# NumPad.net
KiCad netlist of a schematic drawn in EAGLE
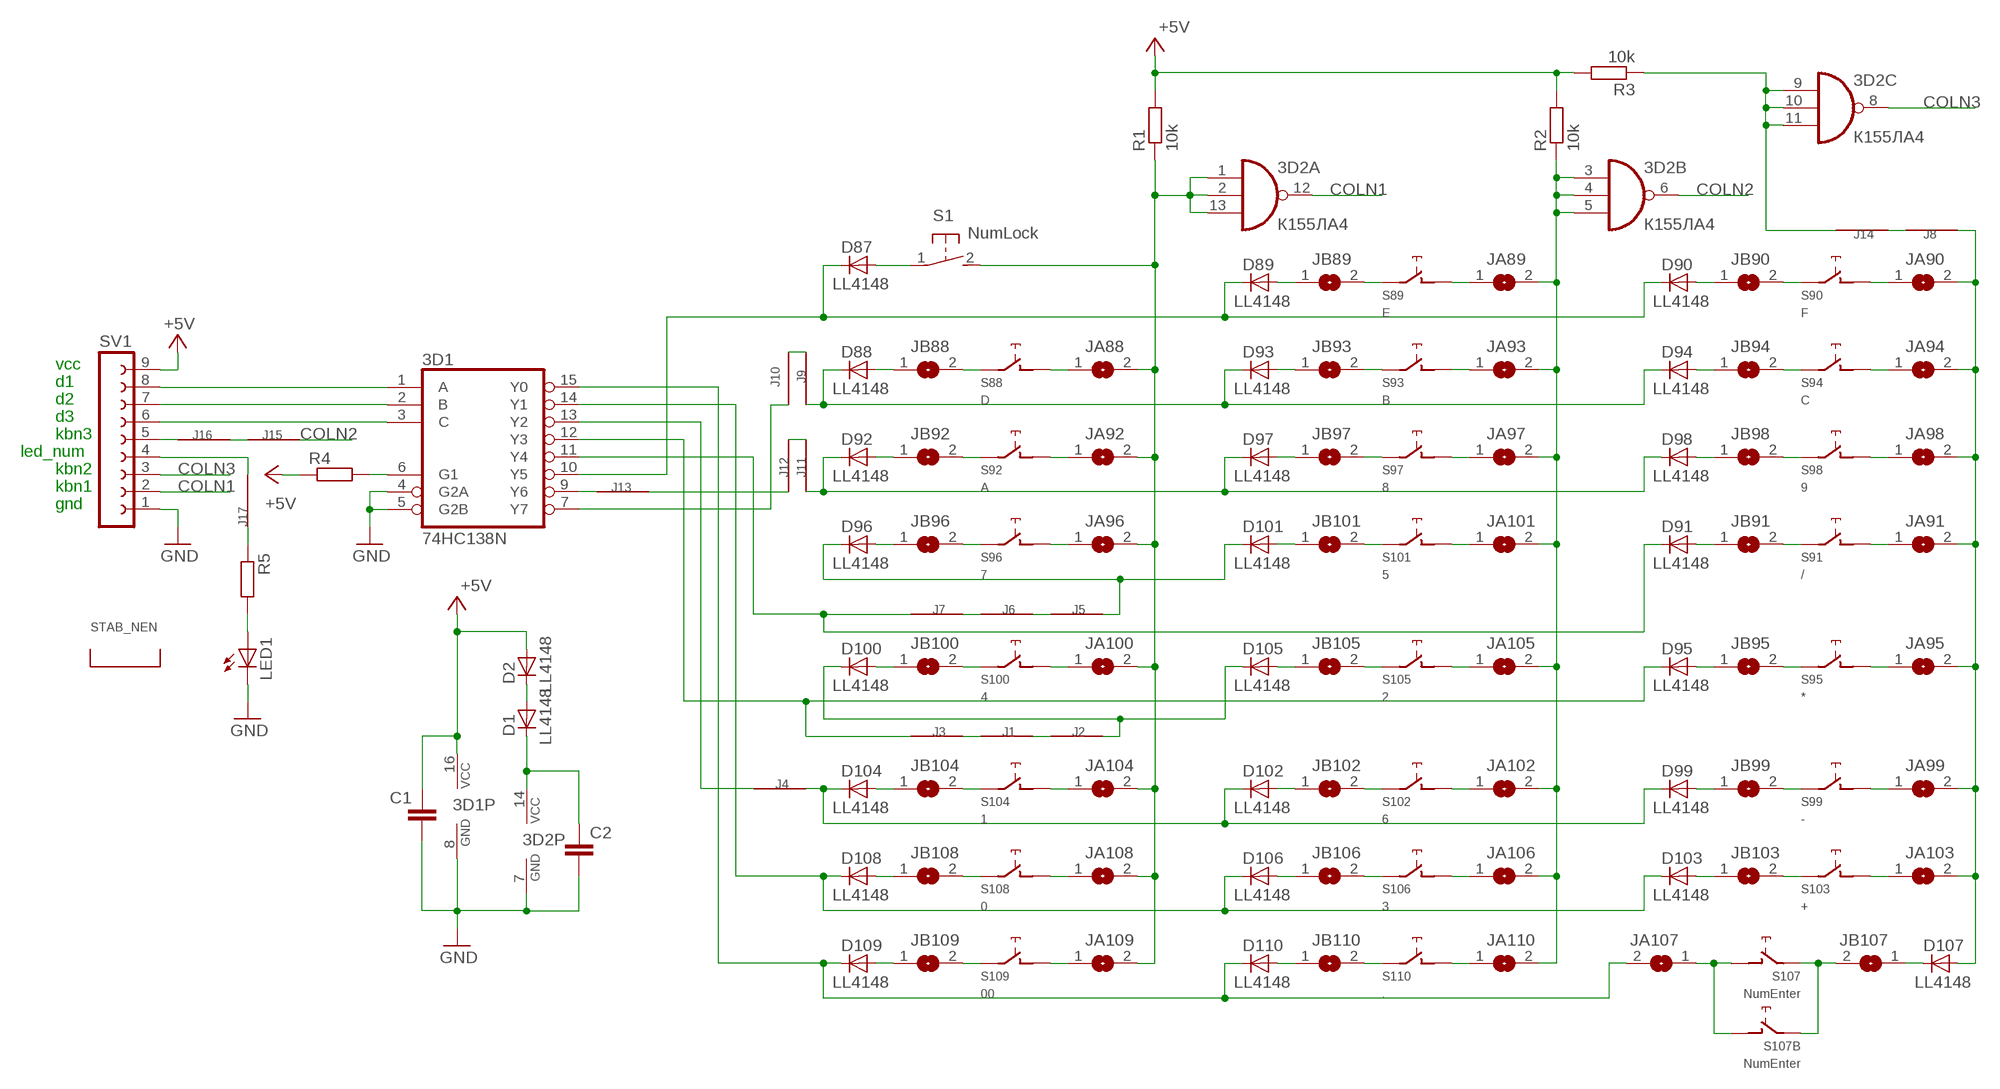
[diagram p0: schematic, sheet 1]

(export (version "E")
  (design (tool "Eeschema 10.0.6"))
  (components
    (comp (ref "3D1")
      (value "74HC138N")
      (footprint "eagle-import:DIL16")
      (libsource (lib "eagle-import") (part "74138NHC"))
    )
    (comp (ref "3D2")
      (value "К155ЛА4")
      (footprint "eagle-import:DIL14")
      (libsource (lib "eagle-import") (part "7410NHC"))
    )
    (comp (ref "C1")
      (value "C-EUC1206")
      (footprint "eagle-import:C1206")
      (libsource (lib "eagle-import") (part "C-EUC1206"))
    )
    (comp (ref "C2")
      (value "C-EUC1206")
      (footprint "eagle-import:C1206")
      (libsource (lib "eagle-import") (part "C-EUC1206"))
    )
    (comp (ref "D1")
      (value "LL4148")
      (footprint "eagle-import:SOD80C")
      (libsource (lib "eagle-import") (part "LL4148"))
    )
    (comp (ref "D2")
      (value "LL4148")
      (footprint "eagle-import:SOD80C")
      (libsource (lib "eagle-import") (part "LL4148"))
    )
    (comp (ref "D87")
      (value "LL4148")
      (footprint "eagle-import:SOD80C")
      (libsource (lib "eagle-import") (part "LL4148"))
    )
    (comp (ref "D88")
      (value "LL4148")
      (footprint "eagle-import:SOD80C")
      (libsource (lib "eagle-import") (part "LL4148"))
    )
    (comp (ref "D89")
      (value "LL4148")
      (footprint "eagle-import:SOD80C")
      (libsource (lib "eagle-import") (part "LL4148"))
    )
    (comp (ref "D90")
      (value "LL4148")
      (footprint "eagle-import:SOD80C")
      (libsource (lib "eagle-import") (part "LL4148"))
    )
    (comp (ref "D91")
      (value "LL4148")
      (footprint "eagle-import:SOD80C")
      (libsource (lib "eagle-import") (part "LL4148"))
    )
    (comp (ref "D92")
      (value "LL4148")
      (footprint "eagle-import:SOD80C")
      (libsource (lib "eagle-import") (part "LL4148"))
    )
    (comp (ref "D93")
      (value "LL4148")
      (footprint "eagle-import:SOD80C")
      (libsource (lib "eagle-import") (part "LL4148"))
    )
    (comp (ref "D94")
      (value "LL4148")
      (footprint "eagle-import:SOD80C")
      (libsource (lib "eagle-import") (part "LL4148"))
    )
    (comp (ref "D95")
      (value "LL4148")
      (footprint "eagle-import:SOD80C")
      (libsource (lib "eagle-import") (part "LL4148"))
    )
    (comp (ref "D96")
      (value "LL4148")
      (footprint "eagle-import:SOD80C")
      (libsource (lib "eagle-import") (part "LL4148"))
    )
    (comp (ref "D97")
      (value "LL4148")
      (footprint "eagle-import:SOD80C")
      (libsource (lib "eagle-import") (part "LL4148"))
    )
    (comp (ref "D98")
      (value "LL4148")
      (footprint "eagle-import:SOD80C")
      (libsource (lib "eagle-import") (part "LL4148"))
    )
    (comp (ref "D99")
      (value "LL4148")
      (footprint "eagle-import:SOD80C")
      (libsource (lib "eagle-import") (part "LL4148"))
    )
    (comp (ref "D100")
      (value "LL4148")
      (footprint "eagle-import:SOD80C")
      (libsource (lib "eagle-import") (part "LL4148"))
    )
    (comp (ref "D101")
      (value "LL4148")
      (footprint "eagle-import:SOD80C")
      (libsource (lib "eagle-import") (part "LL4148"))
    )
    (comp (ref "D102")
      (value "LL4148")
      (footprint "eagle-import:SOD80C")
      (libsource (lib "eagle-import") (part "LL4148"))
    )
    (comp (ref "D103")
      (value "LL4148")
      (footprint "eagle-import:SOD80C")
      (libsource (lib "eagle-import") (part "LL4148"))
    )
    (comp (ref "D104")
      (value "LL4148")
      (footprint "eagle-import:SOD80C")
      (libsource (lib "eagle-import") (part "LL4148"))
    )
    (comp (ref "D105")
      (value "LL4148")
      (footprint "eagle-import:SOD80C")
      (libsource (lib "eagle-import") (part "LL4148"))
    )
    (comp (ref "D106")
      (value "LL4148")
      (footprint "eagle-import:SOD80C")
      (libsource (lib "eagle-import") (part "LL4148"))
    )
    (comp (ref "D107")
      (value "LL4148")
      (footprint "eagle-import:SOD80C")
      (libsource (lib "eagle-import") (part "LL4148"))
    )
    (comp (ref "D108")
      (value "LL4148")
      (footprint "eagle-import:SOD80C")
      (libsource (lib "eagle-import") (part "LL4148"))
    )
    (comp (ref "D109")
      (value "LL4148")
      (footprint "eagle-import:SOD80C")
      (libsource (lib "eagle-import") (part "LL4148"))
    )
    (comp (ref "D110")
      (value "LL4148")
      (footprint "eagle-import:SOD80C")
      (libsource (lib "eagle-import") (part "LL4148"))
    )
    (comp (ref "J1")
      (value "J")
      (footprint "eagle-import:R1206W")
      (libsource (lib "eagle-import") (part "J"))
    )
    (comp (ref "J2")
      (value "J")
      (footprint "eagle-import:R1206W")
      (libsource (lib "eagle-import") (part "J"))
    )
    (comp (ref "J3")
      (value "J")
      (footprint "eagle-import:R1206W")
      (libsource (lib "eagle-import") (part "J"))
    )
    (comp (ref "J4")
      (value "J")
      (footprint "eagle-import:R1206W")
      (libsource (lib "eagle-import") (part "J"))
    )
    (comp (ref "J5")
      (value "J")
      (footprint "eagle-import:R1206W")
      (libsource (lib "eagle-import") (part "J"))
    )
    (comp (ref "J6")
      (value "J")
      (footprint "eagle-import:R1206W")
      (libsource (lib "eagle-import") (part "J"))
    )
    (comp (ref "J7")
      (value "J")
      (footprint "eagle-import:R1206W")
      (libsource (lib "eagle-import") (part "J"))
    )
    (comp (ref "J8")
      (value "J")
      (footprint "eagle-import:R1206W")
      (libsource (lib "eagle-import") (part "J"))
    )
    (comp (ref "J9")
      (value "J")
      (footprint "eagle-import:R1206W")
      (libsource (lib "eagle-import") (part "J"))
    )
    (comp (ref "J10")
      (value "J")
      (footprint "eagle-import:R1206W")
      (libsource (lib "eagle-import") (part "J"))
    )
    (comp (ref "J11")
      (value "J")
      (footprint "eagle-import:R1206W")
      (libsource (lib "eagle-import") (part "J"))
    )
    (comp (ref "J12")
      (value "J")
      (footprint "eagle-import:R1206W")
      (libsource (lib "eagle-import") (part "J"))
    )
    (comp (ref "J13")
      (value "J")
      (footprint "eagle-import:R1206W")
      (libsource (lib "eagle-import") (part "J"))
    )
    (comp (ref "J14")
      (value "J")
      (footprint "eagle-import:R1206W")
      (libsource (lib "eagle-import") (part "J"))
    )
    (comp (ref "J15")
      (value "J")
      (footprint "eagle-import:R1206W")
      (libsource (lib "eagle-import") (part "J"))
    )
    (comp (ref "J16")
      (value "J")
      (footprint "eagle-import:R1206W")
      (libsource (lib "eagle-import") (part "J"))
    )
    (comp (ref "J17")
      (value "J")
      (footprint "eagle-import:R1206W")
      (libsource (lib "eagle-import") (part "J"))
    )
    (comp (ref "JA88")
      (value "SJ")
      (footprint "eagle-import:SJ")
      (libsource (lib "eagle-import") (part "SJ"))
    )
    (comp (ref "JA89")
      (value "SJ")
      (footprint "eagle-import:SJ")
      (libsource (lib "eagle-import") (part "SJ"))
    )
    (comp (ref "JA90")
      (value "SJ")
      (footprint "eagle-import:SJ")
      (libsource (lib "eagle-import") (part "SJ"))
    )
    (comp (ref "JA91")
      (value "SJ")
      (footprint "eagle-import:SJ")
      (libsource (lib "eagle-import") (part "SJ"))
    )
    (comp (ref "JA92")
      (value "SJ")
      (footprint "eagle-import:SJ")
      (libsource (lib "eagle-import") (part "SJ"))
    )
    (comp (ref "JA93")
      (value "SJ")
      (footprint "eagle-import:SJ")
      (libsource (lib "eagle-import") (part "SJ"))
    )
    (comp (ref "JA94")
      (value "SJ")
      (footprint "eagle-import:SJ")
      (libsource (lib "eagle-import") (part "SJ"))
    )
    (comp (ref "JA95")
      (value "SJ")
      (footprint "eagle-import:SJ")
      (libsource (lib "eagle-import") (part "SJ"))
    )
    (comp (ref "JA96")
      (value "SJ")
      (footprint "eagle-import:SJ")
      (libsource (lib "eagle-import") (part "SJ"))
    )
    (comp (ref "JA97")
      (value "SJ")
      (footprint "eagle-import:SJ")
      (libsource (lib "eagle-import") (part "SJ"))
    )
    (comp (ref "JA98")
      (value "SJ")
      (footprint "eagle-import:SJ")
      (libsource (lib "eagle-import") (part "SJ"))
    )
    (comp (ref "JA99")
      (value "SJ")
      (footprint "eagle-import:SJ")
      (libsource (lib "eagle-import") (part "SJ"))
    )
    (comp (ref "JA100")
      (value "SJ")
      (footprint "eagle-import:SJ")
      (libsource (lib "eagle-import") (part "SJ"))
    )
    (comp (ref "JA101")
      (value "SJ")
      (footprint "eagle-import:SJ")
      (libsource (lib "eagle-import") (part "SJ"))
    )
    (comp (ref "JA102")
      (value "SJ")
      (footprint "eagle-import:SJ")
      (libsource (lib "eagle-import") (part "SJ"))
    )
    (comp (ref "JA103")
      (value "SJ")
      (footprint "eagle-import:SJ")
      (libsource (lib "eagle-import") (part "SJ"))
    )
    (comp (ref "JA104")
      (value "SJ")
      (footprint "eagle-import:SJ")
      (libsource (lib "eagle-import") (part "SJ"))
    )
    (comp (ref "JA105")
      (value "SJ")
      (footprint "eagle-import:SJ")
      (libsource (lib "eagle-import") (part "SJ"))
    )
    (comp (ref "JA106")
      (value "SJ")
      (footprint "eagle-import:SJ")
      (libsource (lib "eagle-import") (part "SJ"))
    )
    (comp (ref "JA107")
      (value "SJ")
      (footprint "eagle-import:SJ")
      (libsource (lib "eagle-import") (part "SJ"))
    )
    (comp (ref "JA108")
      (value "SJ")
      (footprint "eagle-import:SJ")
      (libsource (lib "eagle-import") (part "SJ"))
    )
    (comp (ref "JA109")
      (value "SJ")
      (footprint "eagle-import:SJ")
      (libsource (lib "eagle-import") (part "SJ"))
    )
    (comp (ref "JA110")
      (value "SJ")
      (footprint "eagle-import:SJ")
      (libsource (lib "eagle-import") (part "SJ"))
    )
    (comp (ref "JB88")
      (value "SJ")
      (footprint "eagle-import:SJ")
      (libsource (lib "eagle-import") (part "SJ"))
    )
    (comp (ref "JB89")
      (value "SJ")
      (footprint "eagle-import:SJ")
      (libsource (lib "eagle-import") (part "SJ"))
    )
    (comp (ref "JB90")
      (value "SJ")
      (footprint "eagle-import:SJ")
      (libsource (lib "eagle-import") (part "SJ"))
    )
    (comp (ref "JB91")
      (value "SJ")
      (footprint "eagle-import:SJ")
      (libsource (lib "eagle-import") (part "SJ"))
    )
    (comp (ref "JB92")
      (value "SJ")
      (footprint "eagle-import:SJ")
      (libsource (lib "eagle-import") (part "SJ"))
    )
    (comp (ref "JB93")
      (value "SJ")
      (footprint "eagle-import:SJ")
      (libsource (lib "eagle-import") (part "SJ"))
    )
    (comp (ref "JB94")
      (value "SJ")
      (footprint "eagle-import:SJ")
      (libsource (lib "eagle-import") (part "SJ"))
    )
    (comp (ref "JB95")
      (value "SJ")
      (footprint "eagle-import:SJ")
      (libsource (lib "eagle-import") (part "SJ"))
    )
    (comp (ref "JB96")
      (value "SJ")
      (footprint "eagle-import:SJ")
      (libsource (lib "eagle-import") (part "SJ"))
    )
    (comp (ref "JB97")
      (value "SJ")
      (footprint "eagle-import:SJ")
      (libsource (lib "eagle-import") (part "SJ"))
    )
    (comp (ref "JB98")
      (value "SJ")
      (footprint "eagle-import:SJ")
      (libsource (lib "eagle-import") (part "SJ"))
    )
    (comp (ref "JB99")
      (value "SJ")
      (footprint "eagle-import:SJ")
      (libsource (lib "eagle-import") (part "SJ"))
    )
    (comp (ref "JB100")
      (value "SJ")
      (footprint "eagle-import:SJ")
      (libsource (lib "eagle-import") (part "SJ"))
    )
    (comp (ref "JB101")
      (value "SJ")
      (footprint "eagle-import:SJ")
      (libsource (lib "eagle-import") (part "SJ"))
    )
    (comp (ref "JB102")
      (value "SJ")
      (footprint "eagle-import:SJ")
      (libsource (lib "eagle-import") (part "SJ"))
    )
    (comp (ref "JB103")
      (value "SJ")
      (footprint "eagle-import:SJ")
      (libsource (lib "eagle-import") (part "SJ"))
    )
    (comp (ref "JB104")
      (value "SJ")
      (footprint "eagle-import:SJ")
      (libsource (lib "eagle-import") (part "SJ"))
    )
    (comp (ref "JB105")
      (value "SJ")
      (footprint "eagle-import:SJ")
      (libsource (lib "eagle-import") (part "SJ"))
    )
    (comp (ref "JB106")
      (value "SJ")
      (footprint "eagle-import:SJ")
      (libsource (lib "eagle-import") (part "SJ"))
    )
    (comp (ref "JB107")
      (value "SJ")
      (footprint "eagle-import:SJ")
      (libsource (lib "eagle-import") (part "SJ"))
    )
    (comp (ref "JB108")
      (value "SJ")
      (footprint "eagle-import:SJ")
      (libsource (lib "eagle-import") (part "SJ"))
    )
    (comp (ref "JB109")
      (value "SJ")
      (footprint "eagle-import:SJ")
      (libsource (lib "eagle-import") (part "SJ"))
    )
    (comp (ref "JB110")
      (value "SJ")
      (footprint "eagle-import:SJ")
      (libsource (lib "eagle-import") (part "SJ"))
    )
    (comp (ref "LED1")
      (value "LED5MM")
      (footprint "eagle-import:LED5MM")
      (libsource (lib "eagle-import") (part "LED5MM"))
    )
    (comp (ref "R1")
      (value "10k")
      (footprint "eagle-import:R1206W")
      (libsource (lib "eagle-import") (part "R-EU_R1206W"))
    )
    (comp (ref "R2")
      (value "10k")
      (footprint "eagle-import:R1206W")
      (libsource (lib "eagle-import") (part "R-EU_R1206W"))
    )
    (comp (ref "R3")
      (value "10k")
      (footprint "eagle-import:R1206W")
      (libsource (lib "eagle-import") (part "R-EU_R1206W"))
    )
    (comp (ref "R4")
      (value "R-EU_R1206W")
      (footprint "eagle-import:R1206W")
      (libsource (lib "eagle-import") (part "R-EU_R1206W"))
    )
    (comp (ref "R5")
      (value "R-EU_R1206W")
      (footprint "eagle-import:R1206W")
      (libsource (lib "eagle-import") (part "R-EU_R1206W"))
    )
    (comp (ref "S1")
      (value "NumLock")
      (footprint "eagle-import:B3F-31XX")
      (fields (field (name "MPN") "B3F-3100"))
      (libsource (lib "eagle-import") (part "31-XX"))
    )
    (comp (ref "S88")
      (value "D")
      (footprint "eagle-import:CHERRY-MX-4P")
      (libsource (lib "eagle-import") (part "CHERRY-MX-4P"))
    )
    (comp (ref "S89")
      (value "E")
      (footprint "eagle-import:CHERRY-MX-4P")
      (libsource (lib "eagle-import") (part "CHERRY-MX-4P"))
    )
    (comp (ref "S90")
      (value "F")
      (footprint "eagle-import:CHERRY-MX-4P")
      (libsource (lib "eagle-import") (part "CHERRY-MX-4P"))
    )
    (comp (ref "S91")
      (value "/")
      (footprint "eagle-import:CHERRY-MX-4P")
      (libsource (lib "eagle-import") (part "CHERRY-MX-4P"))
    )
    (comp (ref "S92")
      (value "A")
      (footprint "eagle-import:CHERRY-MX-4P")
      (libsource (lib "eagle-import") (part "CHERRY-MX-4P"))
    )
    (comp (ref "S93")
      (value "B")
      (footprint "eagle-import:CHERRY-MX-4P")
      (libsource (lib "eagle-import") (part "CHERRY-MX-4P"))
    )
    (comp (ref "S94")
      (value "C")
      (footprint "eagle-import:CHERRY-MX-4P")
      (libsource (lib "eagle-import") (part "CHERRY-MX-4P"))
    )
    (comp (ref "S95")
      (value "*")
      (footprint "eagle-import:CHERRY-MX-4P")
      (libsource (lib "eagle-import") (part "CHERRY-MX-4P"))
    )
    (comp (ref "S96")
      (value "7")
      (footprint "eagle-import:CHERRY-MX-4P")
      (libsource (lib "eagle-import") (part "CHERRY-MX-4P"))
    )
    (comp (ref "S97")
      (value "8")
      (footprint "eagle-import:CHERRY-MX-4P")
      (libsource (lib "eagle-import") (part "CHERRY-MX-4P"))
    )
    (comp (ref "S98")
      (value "9")
      (footprint "eagle-import:CHERRY-MX-4P")
      (libsource (lib "eagle-import") (part "CHERRY-MX-4P"))
    )
    (comp (ref "S99")
      (value "-")
      (footprint "eagle-import:CHERRY-MX-4P")
      (libsource (lib "eagle-import") (part "CHERRY-MX-4P"))
    )
    (comp (ref "S100")
      (value "4")
      (footprint "eagle-import:CHERRY-MX-4P")
      (libsource (lib "eagle-import") (part "CHERRY-MX-4P"))
    )
    (comp (ref "S101")
      (value "5")
      (footprint "eagle-import:CHERRY-MX-4P")
      (libsource (lib "eagle-import") (part "CHERRY-MX-4P"))
    )
    (comp (ref "S102")
      (value "6")
      (footprint "eagle-import:CHERRY-MX-4P")
      (libsource (lib "eagle-import") (part "CHERRY-MX-4P"))
    )
    (comp (ref "S103")
      (value "+")
      (footprint "eagle-import:CHERRY-MX-4P")
      (libsource (lib "eagle-import") (part "CHERRY-MX-4P"))
    )
    (comp (ref "S104")
      (value "1")
      (footprint "eagle-import:CHERRY-MX-4P")
      (libsource (lib "eagle-import") (part "CHERRY-MX-4P"))
    )
    (comp (ref "S105")
      (value "2")
      (footprint "eagle-import:CHERRY-MX-4P")
      (libsource (lib "eagle-import") (part "CHERRY-MX-4P"))
    )
    (comp (ref "S106")
      (value "3")
      (footprint "eagle-import:CHERRY-MX-4P")
      (libsource (lib "eagle-import") (part "CHERRY-MX-4P"))
    )
    (comp (ref "S107")
      (value "NumEnter")
      (footprint "eagle-import:CHERRY-MX-4P")
      (libsource (lib "eagle-import") (part "CHERRY-MX-4P"))
    )
    (comp (ref "S107B")
      (value "NumEnter")
      (footprint "eagle-import:CHERRY-MX-4P")
      (libsource (lib "eagle-import") (part "CHERRY-MX-4P"))
    )
    (comp (ref "S108")
      (value "0")
      (footprint "eagle-import:CHERRY-MX-4P")
      (libsource (lib "eagle-import") (part "CHERRY-MX-4P"))
    )
    (comp (ref "S109")
      (value "00")
      (footprint "eagle-import:CHERRY-MX-4P")
      (libsource (lib "eagle-import") (part "CHERRY-MX-4P"))
    )
    (comp (ref "S110")
      (value ".")
      (footprint "eagle-import:CHERRY-MX-4P")
      (libsource (lib "eagle-import") (part "CHERRY-MX-4P"))
    )
    (comp (ref "STAB_NEN")
      (value "STAB")
      (footprint "eagle-import:ZEALIOS-PCB_2U")
      (libsource (lib "eagle-import") (part "STAB"))
    )
    (comp (ref "SV1")
      (value "FE09-1")
      (footprint "eagle-import:FE09")
      (libsource (lib "eagle-import") (part "FE09-1"))
    )
  )
  (nets
    (net (code "1") (name "+5V") (class "Default")
      (node (ref "3D1") (pin "16") (pinfunction "VCC_16") (pintype "power_in"))
      (node (ref "C1") (pin "1") (pinfunction "1_1") (pintype "passive"))
      (node (ref "D2") (pin "A") (pinfunction "A_A") (pintype "passive"))
      (node (ref "R1") (pin "2") (pinfunction "2_2") (pintype "passive"))
      (node (ref "R2") (pin "2") (pinfunction "2_2") (pintype "passive"))
      (node (ref "R3") (pin "2") (pinfunction "2_2") (pintype "passive"))
      (node (ref "R4") (pin "1") (pinfunction "1_1") (pintype "passive"))
      (node (ref "SV1") (pin "9") (pinfunction "9_9") (pintype "passive"))
    )
    (net (code "2") (name "/COLN1") (class "Default")
      (node (ref "3D2") (pin "12") (pinfunction "O_12") (pintype "output"))
      (node (ref "SV1") (pin "2") (pinfunction "2_2") (pintype "passive"))
    )
    (net (code "3") (name "/COLN2") (class "Default")
      (node (ref "3D2") (pin "6") (pinfunction "O_6") (pintype "output"))
      (node (ref "J15") (pin "1") (pinfunction "P$1_1") (pintype "bidirectional"))
    )
    (net (code "4") (name "/COLN3") (class "Default")
      (node (ref "3D2") (pin "8") (pinfunction "O_8") (pintype "output"))
      (node (ref "SV1") (pin "3") (pinfunction "3_3") (pintype "passive"))
    )
    (net (code "5") (name "GND") (class "Default")
      (node (ref "3D1") (pin "4") (pinfunction "G2A_4") (pintype "input"))
      (node (ref "3D1") (pin "5") (pinfunction "G2B_5") (pintype "input"))
      (node (ref "3D1") (pin "8") (pinfunction "GND_8") (pintype "power_in"))
      (node (ref "3D2") (pin "7") (pinfunction "GND_7") (pintype "power_in"))
      (node (ref "C1") (pin "2") (pinfunction "2_2") (pintype "passive"))
      (node (ref "C2") (pin "2") (pinfunction "2_2") (pintype "passive"))
      (node (ref "LED1") (pin "K") (pinfunction "C_K") (pintype "passive"))
      (node (ref "SV1") (pin "1") (pinfunction "1_1") (pintype "passive"))
    )
    (net (code "6") (name "Net-(3D1A-A)") (class "Default")
      (node (ref "3D1") (pin "1") (pinfunction "A_1") (pintype "input"))
      (node (ref "SV1") (pin "8") (pinfunction "8_8") (pintype "passive"))
    )
    (net (code "7") (name "Net-(3D1A-B)") (class "Default")
      (node (ref "3D1") (pin "2") (pinfunction "B_2") (pintype "input"))
      (node (ref "SV1") (pin "7") (pinfunction "7_7") (pintype "passive"))
    )
    (net (code "8") (name "Net-(3D1A-C)") (class "Default")
      (node (ref "3D1") (pin "3") (pinfunction "C_3") (pintype "input"))
      (node (ref "SV1") (pin "6") (pinfunction "6_6") (pintype "passive"))
    )
    (net (code "9") (name "Net-(3D1A-G1)") (class "Default")
      (node (ref "3D1") (pin "6") (pinfunction "G1_6") (pintype "input"))
      (node (ref "R4") (pin "2") (pinfunction "2_2") (pintype "passive"))
    )
    (net (code "10") (name "Net-(3D1A-Y0)") (class "Default")
      (node (ref "3D1") (pin "15") (pinfunction "Y0_15") (pintype "output"))
      (node (ref "D109") (pin "C") (pinfunction "C_C") (pintype "passive"))
      (node (ref "D110") (pin "C") (pinfunction "C_C") (pintype "passive"))
      (node (ref "JA107") (pin "2") (pinfunction "2_2") (pintype "passive"))
    )
    (net (code "11") (name "Net-(3D1A-Y1)") (class "Default")
      (node (ref "3D1") (pin "14") (pinfunction "Y1_14") (pintype "output"))
      (node (ref "D103") (pin "C") (pinfunction "C_C") (pintype "passive"))
      (node (ref "D106") (pin "C") (pinfunction "C_C") (pintype "passive"))
      (node (ref "D108") (pin "C") (pinfunction "C_C") (pintype "passive"))
    )
    (net (code "12") (name "Net-(3D1A-Y2)") (class "Default")
      (node (ref "3D1") (pin "13") (pinfunction "Y2_13") (pintype "output"))
      (node (ref "J4") (pin "2") (pinfunction "P$2_2") (pintype "bidirectional"))
    )
    (net (code "13") (name "Net-(3D1A-Y3)") (class "Default")
      (node (ref "3D1") (pin "12") (pinfunction "Y3_12") (pintype "output"))
      (node (ref "D95") (pin "C") (pinfunction "C_C") (pintype "passive"))
      (node (ref "J3") (pin "2") (pinfunction "P$2_2") (pintype "bidirectional"))
    )
    (net (code "14") (name "Net-(3D1A-Y4)") (class "Default")
      (node (ref "3D1") (pin "11") (pinfunction "Y4_11") (pintype "output"))
      (node (ref "D91") (pin "C") (pinfunction "C_C") (pintype "passive"))
      (node (ref "J7") (pin "2") (pinfunction "P$2_2") (pintype "bidirectional"))
    )
    (net (code "15") (name "Net-(3D1A-Y5)") (class "Default")
      (node (ref "3D1") (pin "10") (pinfunction "Y5_10") (pintype "output"))
      (node (ref "D87") (pin "C") (pinfunction "C_C") (pintype "passive"))
      (node (ref "D89") (pin "C") (pinfunction "C_C") (pintype "passive"))
      (node (ref "D90") (pin "C") (pinfunction "C_C") (pintype "passive"))
    )
    (net (code "16") (name "Net-(3D1A-Y6)") (class "Default")
      (node (ref "3D1") (pin "9") (pinfunction "Y6_9") (pintype "output"))
      (node (ref "J13") (pin "2") (pinfunction "P$2_2") (pintype "bidirectional"))
    )
    (net (code "17") (name "Net-(3D1A-Y7)") (class "Default")
      (node (ref "3D1") (pin "7") (pinfunction "Y7_7") (pintype "output"))
      (node (ref "J10") (pin "1") (pinfunction "P$1_1") (pintype "bidirectional"))
    )
    (net (code "18") (name "Net-(3D2A-I0)") (class "Default")
      (node (ref "3D2") (pin "1") (pinfunction "I0_1") (pintype "input"))
      (node (ref "3D2") (pin "13") (pinfunction "I2_13") (pintype "input"))
      (node (ref "3D2") (pin "2") (pinfunction "I1_2") (pintype "input"))
      (node (ref "JA100") (pin "2") (pinfunction "2_2") (pintype "passive"))
      (node (ref "JA104") (pin "2") (pinfunction "2_2") (pintype "passive"))
      (node (ref "JA108") (pin "2") (pinfunction "2_2") (pintype "passive"))
      (node (ref "JA109") (pin "2") (pinfunction "2_2") (pintype "passive"))
      (node (ref "JA88") (pin "2") (pinfunction "2_2") (pintype "passive"))
      (node (ref "JA92") (pin "2") (pinfunction "2_2") (pintype "passive"))
      (node (ref "JA96") (pin "2") (pinfunction "2_2") (pintype "passive"))
      (node (ref "R1") (pin "1") (pinfunction "1_1") (pintype "passive"))
      (node (ref "S1") (pin "2") (pinfunction "S_2") (pintype "passive"))
    )
    (net (code "19") (name "Net-(3D2B-I0)") (class "Default")
      (node (ref "3D2") (pin "3") (pinfunction "I0_3") (pintype "input"))
      (node (ref "3D2") (pin "4") (pinfunction "I1_4") (pintype "input"))
      (node (ref "3D2") (pin "5") (pinfunction "I2_5") (pintype "input"))
      (node (ref "JA101") (pin "2") (pinfunction "2_2") (pintype "passive"))
      (node (ref "JA102") (pin "2") (pinfunction "2_2") (pintype "passive"))
      (node (ref "JA105") (pin "2") (pinfunction "2_2") (pintype "passive"))
      (node (ref "JA106") (pin "2") (pinfunction "2_2") (pintype "passive"))
      (node (ref "JA110") (pin "2") (pinfunction "2_2") (pintype "passive"))
      (node (ref "JA89") (pin "2") (pinfunction "2_2") (pintype "passive"))
      (node (ref "JA93") (pin "2") (pinfunction "2_2") (pintype "passive"))
      (node (ref "JA97") (pin "2") (pinfunction "2_2") (pintype "passive"))
      (node (ref "R2") (pin "1") (pinfunction "1_1") (pintype "passive"))
    )
    (net (code "20") (name "Net-(3D2C-I0)") (class "Default")
      (node (ref "3D2") (pin "10") (pinfunction "I1_10") (pintype "input"))
      (node (ref "3D2") (pin "11") (pinfunction "I2_11") (pintype "input"))
      (node (ref "3D2") (pin "9") (pinfunction "I0_9") (pintype "input"))
      (node (ref "J14") (pin "1") (pinfunction "P$1_1") (pintype "bidirectional"))
      (node (ref "R3") (pin "1") (pinfunction "1_1") (pintype "passive"))
    )
    (net (code "21") (name "Net-(3D2D-VCC)") (class "Default")
      (node (ref "3D2") (pin "14") (pinfunction "VCC_14") (pintype "power_in"))
      (node (ref "C2") (pin "1") (pinfunction "1_1") (pintype "passive"))
      (node (ref "D1") (pin "C") (pinfunction "C_C") (pintype "passive"))
    )
    (net (code "22") (name "Net-(D1-PadA)") (class "Default")
      (node (ref "D1") (pin "A") (pinfunction "A_A") (pintype "passive"))
      (node (ref "D2") (pin "C") (pinfunction "C_C") (pintype "passive"))
    )
    (net (code "23") (name "Net-(D88-PadA)") (class "Default")
      (node (ref "D88") (pin "A") (pinfunction "A_A") (pintype "passive"))
      (node (ref "JB88") (pin "1") (pinfunction "1_1") (pintype "passive"))
    )
    (net (code "24") (name "Net-(D89-PadA)") (class "Default")
      (node (ref "D89") (pin "A") (pinfunction "A_A") (pintype "passive"))
      (node (ref "JB89") (pin "1") (pinfunction "1_1") (pintype "passive"))
    )
    (net (code "25") (name "Net-(D90-PadA)") (class "Default")
      (node (ref "D90") (pin "A") (pinfunction "A_A") (pintype "passive"))
      (node (ref "JB90") (pin "1") (pinfunction "1_1") (pintype "passive"))
    )
    (net (code "26") (name "Net-(D91-PadA)") (class "Default")
      (node (ref "D91") (pin "A") (pinfunction "A_A") (pintype "passive"))
      (node (ref "JB91") (pin "1") (pinfunction "1_1") (pintype "passive"))
    )
    (net (code "27") (name "Net-(D92-PadA)") (class "Default")
      (node (ref "D92") (pin "A") (pinfunction "A_A") (pintype "passive"))
      (node (ref "JB92") (pin "1") (pinfunction "1_1") (pintype "passive"))
    )
    (net (code "28") (name "Net-(D93-PadA)") (class "Default")
      (node (ref "D93") (pin "A") (pinfunction "A_A") (pintype "passive"))
      (node (ref "JB93") (pin "1") (pinfunction "1_1") (pintype "passive"))
    )
    (net (code "29") (name "Net-(D94-PadA)") (class "Default")
      (node (ref "D94") (pin "A") (pinfunction "A_A") (pintype "passive"))
      (node (ref "JB94") (pin "1") (pinfunction "1_1") (pintype "passive"))
    )
    (net (code "30") (name "Net-(D95-PadA)") (class "Default")
      (node (ref "D95") (pin "A") (pinfunction "A_A") (pintype "passive"))
      (node (ref "JB95") (pin "1") (pinfunction "1_1") (pintype "passive"))
    )
    (net (code "31") (name "Net-(D96-PadA)") (class "Default")
      (node (ref "D96") (pin "A") (pinfunction "A_A") (pintype "passive"))
      (node (ref "JB96") (pin "1") (pinfunction "1_1") (pintype "passive"))
    )
    (net (code "32") (name "Net-(D97-PadA)") (class "Default")
      (node (ref "D97") (pin "A") (pinfunction "A_A") (pintype "passive"))
      (node (ref "JB97") (pin "1") (pinfunction "1_1") (pintype "passive"))
    )
    (net (code "33") (name "Net-(D98-PadA)") (class "Default")
      (node (ref "D98") (pin "A") (pinfunction "A_A") (pintype "passive"))
      (node (ref "JB98") (pin "1") (pinfunction "1_1") (pintype "passive"))
    )
    (net (code "34") (name "Net-(D99-PadA)") (class "Default")
      (node (ref "D99") (pin "A") (pinfunction "A_A") (pintype "passive"))
      (node (ref "JB99") (pin "1") (pinfunction "1_1") (pintype "passive"))
    )
    (net (code "35") (name "Net-(D100-PadA)") (class "Default")
      (node (ref "D100") (pin "A") (pinfunction "A_A") (pintype "passive"))
      (node (ref "JB100") (pin "1") (pinfunction "1_1") (pintype "passive"))
    )
    (net (code "36") (name "Net-(D101-PadA)") (class "Default")
      (node (ref "D101") (pin "A") (pinfunction "A_A") (pintype "passive"))
      (node (ref "JB101") (pin "1") (pinfunction "1_1") (pintype "passive"))
    )
    (net (code "37") (name "Net-(D102-PadA)") (class "Default")
      (node (ref "D102") (pin "A") (pinfunction "A_A") (pintype "passive"))
      (node (ref "JB102") (pin "1") (pinfunction "1_1") (pintype "passive"))
    )
    (net (code "38") (name "Net-(D103-PadA)") (class "Default")
      (node (ref "D103") (pin "A") (pinfunction "A_A") (pintype "passive"))
      (node (ref "JB103") (pin "1") (pinfunction "1_1") (pintype "passive"))
    )
    (net (code "39") (name "Net-(D104-PadA)") (class "Default")
      (node (ref "D104") (pin "A") (pinfunction "A_A") (pintype "passive"))
      (node (ref "JB104") (pin "1") (pinfunction "1_1") (pintype "passive"))
    )
    (net (code "40") (name "Net-(D105-PadA)") (class "Default")
      (node (ref "D105") (pin "A") (pinfunction "A_A") (pintype "passive"))
      (node (ref "JB105") (pin "1") (pinfunction "1_1") (pintype "passive"))
    )
    (net (code "41") (name "Net-(D106-PadA)") (class "Default")
      (node (ref "D106") (pin "A") (pinfunction "A_A") (pintype "passive"))
      (node (ref "JB106") (pin "1") (pinfunction "1_1") (pintype "passive"))
    )
    (net (code "42") (name "Net-(D107-PadC)") (class "Default")
      (node (ref "D107") (pin "C") (pinfunction "C_C") (pintype "passive"))
      (node (ref "JB107") (pin "1") (pinfunction "1_1") (pintype "passive"))
    )
    (net (code "43") (name "Net-(D108-PadA)") (class "Default")
      (node (ref "D108") (pin "A") (pinfunction "A_A") (pintype "passive"))
      (node (ref "JB108") (pin "1") (pinfunction "1_1") (pintype "passive"))
    )
    (net (code "44") (name "Net-(D109-PadA)") (class "Default")
      (node (ref "D109") (pin "A") (pinfunction "A_A") (pintype "passive"))
      (node (ref "JB109") (pin "1") (pinfunction "1_1") (pintype "passive"))
    )
    (net (code "45") (name "Net-(D110-PadA)") (class "Default")
      (node (ref "D110") (pin "A") (pinfunction "A_A") (pintype "passive"))
      (node (ref "JB110") (pin "1") (pinfunction "1_1") (pintype "passive"))
    )
    (net (code "46") (name "Net-(J1-P$1)") (class "Default")
      (node (ref "J1") (pin "1") (pinfunction "P$1_1") (pintype "bidirectional"))
      (node (ref "J2") (pin "2") (pinfunction "P$2_2") (pintype "bidirectional"))
    )
    (net (code "47") (name "Net-(J1-P$2)") (class "Default")
      (node (ref "J1") (pin "2") (pinfunction "P$2_2") (pintype "bidirectional"))
      (node (ref "J3") (pin "1") (pinfunction "P$1_1") (pintype "bidirectional"))
    )
    (net (code "48") (name "Net-(J2-P$1)") (class "Default")
      (node (ref "D100") (pin "C") (pinfunction "C_C") (pintype "passive"))
      (node (ref "D105") (pin "C") (pinfunction "C_C") (pintype "passive"))
      (node (ref "J2") (pin "1") (pinfunction "P$1_1") (pintype "bidirectional"))
    )
    (net (code "49") (name "Net-(J4-P$1)") (class "Default")
      (node (ref "D102") (pin "C") (pinfunction "C_C") (pintype "passive"))
      (node (ref "D104") (pin "C") (pinfunction "C_C") (pintype "passive"))
      (node (ref "D99") (pin "C") (pinfunction "C_C") (pintype "passive"))
      (node (ref "J4") (pin "1") (pinfunction "P$1_1") (pintype "bidirectional"))
    )
    (net (code "50") (name "Net-(J5-P$1)") (class "Default")
      (node (ref "D101") (pin "C") (pinfunction "C_C") (pintype "passive"))
      (node (ref "D96") (pin "C") (pinfunction "C_C") (pintype "passive"))
      (node (ref "J5") (pin "1") (pinfunction "P$1_1") (pintype "bidirectional"))
    )
    (net (code "51") (name "Net-(J5-P$2)") (class "Default")
      (node (ref "J5") (pin "2") (pinfunction "P$2_2") (pintype "bidirectional"))
      (node (ref "J6") (pin "1") (pinfunction "P$1_1") (pintype "bidirectional"))
    )
    (net (code "52") (name "Net-(J6-P$2)") (class "Default")
      (node (ref "J6") (pin "2") (pinfunction "P$2_2") (pintype "bidirectional"))
      (node (ref "J7") (pin "1") (pinfunction "P$1_1") (pintype "bidirectional"))
    )
    (net (code "53") (name "Net-(J8-P$2)") (class "Default")
      (node (ref "D107") (pin "A") (pinfunction "A_A") (pintype "passive"))
      (node (ref "J8") (pin "2") (pinfunction "P$2_2") (pintype "bidirectional"))
      (node (ref "JA103") (pin "2") (pinfunction "2_2") (pintype "passive"))
      (node (ref "JA90") (pin "2") (pinfunction "2_2") (pintype "passive"))
      (node (ref "JA91") (pin "2") (pinfunction "2_2") (pintype "passive"))
      (node (ref "JA94") (pin "2") (pinfunction "2_2") (pintype "passive"))
      (node (ref "JA95") (pin "2") (pinfunction "2_2") (pintype "passive"))
      (node (ref "JA98") (pin "2") (pinfunction "2_2") (pintype "passive"))
      (node (ref "JA99") (pin "2") (pinfunction "2_2") (pintype "passive"))
    )
    (net (code "54") (name "Net-(J9-P$2)") (class "Default")
      (node (ref "D88") (pin "C") (pinfunction "C_C") (pintype "passive"))
      (node (ref "D93") (pin "C") (pinfunction "C_C") (pintype "passive"))
      (node (ref "D94") (pin "C") (pinfunction "C_C") (pintype "passive"))
      (node (ref "J9") (pin "2") (pinfunction "P$2_2") (pintype "bidirectional"))
    )
    (net (code "55") (name "Net-(J10-P$2)") (class "Default")
      (node (ref "J10") (pin "2") (pinfunction "P$2_2") (pintype "bidirectional"))
      (node (ref "J9") (pin "1") (pinfunction "P$1_1") (pintype "bidirectional"))
    )
    (net (code "56") (name "Net-(J11-P$1)") (class "Default")
      (node (ref "J11") (pin "1") (pinfunction "P$1_1") (pintype "bidirectional"))
      (node (ref "J12") (pin "1") (pinfunction "P$1_1") (pintype "bidirectional"))
    )
    (net (code "57") (name "Net-(J11-P$2)") (class "Default")
      (node (ref "D92") (pin "C") (pinfunction "C_C") (pintype "passive"))
      (node (ref "D97") (pin "C") (pinfunction "C_C") (pintype "passive"))
      (node (ref "D98") (pin "C") (pinfunction "C_C") (pintype "passive"))
      (node (ref "J11") (pin "2") (pinfunction "P$2_2") (pintype "bidirectional"))
    )
    (net (code "58") (name "Net-(J12-P$2)") (class "Default")
      (node (ref "J12") (pin "2") (pinfunction "P$2_2") (pintype "bidirectional"))
      (node (ref "J13") (pin "1") (pinfunction "P$1_1") (pintype "bidirectional"))
    )
    (net (code "59") (name "Net-(J14-P$2)") (class "Default")
      (node (ref "J14") (pin "2") (pinfunction "P$2_2") (pintype "bidirectional"))
      (node (ref "J8") (pin "1") (pinfunction "P$1_1") (pintype "bidirectional"))
    )
    (net (code "60") (name "Net-(J15-P$2)") (class "Default")
      (node (ref "J15") (pin "2") (pinfunction "P$2_2") (pintype "bidirectional"))
      (node (ref "J16") (pin "1") (pinfunction "P$1_1") (pintype "bidirectional"))
    )
    (net (code "61") (name "Net-(J16-P$2)") (class "Default")
      (node (ref "J16") (pin "2") (pinfunction "P$2_2") (pintype "bidirectional"))
      (node (ref "SV1") (pin "5") (pinfunction "5_5") (pintype "passive"))
    )
    (net (code "62") (name "Net-(J17-P$1)") (class "Default")
      (node (ref "J17") (pin "1") (pinfunction "P$1_1") (pintype "bidirectional"))
      (node (ref "R5") (pin "1") (pinfunction "1_1") (pintype "passive"))
    )
    (net (code "63") (name "Net-(J17-P$2)") (class "Default")
      (node (ref "J17") (pin "2") (pinfunction "P$2_2") (pintype "bidirectional"))
      (node (ref "SV1") (pin "4") (pinfunction "4_4") (pintype "passive"))
    )
    (net (code "64") (name "Net-(LED1-PadA)") (class "Default")
      (node (ref "LED1") (pin "A") (pinfunction "A_A") (pintype "passive"))
      (node (ref "R5") (pin "2") (pinfunction "2_2") (pintype "passive"))
    )
    (net (code "65") (name "Net-(S1-P)") (class "Default")
      (node (ref "D87") (pin "A") (pinfunction "A_A") (pintype "passive"))
      (node (ref "S1") (pin "1") (pinfunction "P_1") (pintype "passive"))
    )
    (net (code "66") (name "Net-(S88A-PIN-1)") (class "Default")
      (node (ref "JB88") (pin "2") (pinfunction "2_2") (pintype "passive"))
      (node (ref "S88") (pin "SW1") (pinfunction "PIN-1_SW1") (pintype "passive"))
    )
    (net (code "67") (name "Net-(S88A-PIN-2)") (class "Default")
      (node (ref "JA88") (pin "1") (pinfunction "1_1") (pintype "passive"))
      (node (ref "S88") (pin "SW2") (pinfunction "PIN-2_SW2") (pintype "passive"))
    )
    (net (code "68") (name "Net-(S89A-PIN-1)") (class "Default")
      (node (ref "JB89") (pin "2") (pinfunction "2_2") (pintype "passive"))
      (node (ref "S89") (pin "SW1") (pinfunction "PIN-1_SW1") (pintype "passive"))
    )
    (net (code "69") (name "Net-(S89A-PIN-2)") (class "Default")
      (node (ref "JA89") (pin "1") (pinfunction "1_1") (pintype "passive"))
      (node (ref "S89") (pin "SW2") (pinfunction "PIN-2_SW2") (pintype "passive"))
    )
    (net (code "70") (name "Net-(S90A-PIN-1)") (class "Default")
      (node (ref "JB90") (pin "2") (pinfunction "2_2") (pintype "passive"))
      (node (ref "S90") (pin "SW1") (pinfunction "PIN-1_SW1") (pintype "passive"))
    )
    (net (code "71") (name "Net-(S90A-PIN-2)") (class "Default")
      (node (ref "JA90") (pin "1") (pinfunction "1_1") (pintype "passive"))
      (node (ref "S90") (pin "SW2") (pinfunction "PIN-2_SW2") (pintype "passive"))
    )
    (net (code "72") (name "Net-(S91A-PIN-1)") (class "Default")
      (node (ref "JB91") (pin "2") (pinfunction "2_2") (pintype "passive"))
      (node (ref "S91") (pin "SW1") (pinfunction "PIN-1_SW1") (pintype "passive"))
    )
    (net (code "73") (name "Net-(S91A-PIN-2)") (class "Default")
      (node (ref "JA91") (pin "1") (pinfunction "1_1") (pintype "passive"))
      (node (ref "S91") (pin "SW2") (pinfunction "PIN-2_SW2") (pintype "passive"))
    )
    (net (code "74") (name "Net-(S92A-PIN-1)") (class "Default")
      (node (ref "JB92") (pin "2") (pinfunction "2_2") (pintype "passive"))
      (node (ref "S92") (pin "SW1") (pinfunction "PIN-1_SW1") (pintype "passive"))
    )
    (net (code "75") (name "Net-(S92A-PIN-2)") (class "Default")
      (node (ref "JA92") (pin "1") (pinfunction "1_1") (pintype "passive"))
      (node (ref "S92") (pin "SW2") (pinfunction "PIN-2_SW2") (pintype "passive"))
    )
    (net (code "76") (name "Net-(S93A-PIN-1)") (class "Default")
      (node (ref "JB93") (pin "2") (pinfunction "2_2") (pintype "passive"))
      (node (ref "S93") (pin "SW1") (pinfunction "PIN-1_SW1") (pintype "passive"))
    )
    (net (code "77") (name "Net-(S93A-PIN-2)") (class "Default")
      (node (ref "JA93") (pin "1") (pinfunction "1_1") (pintype "passive"))
      (node (ref "S93") (pin "SW2") (pinfunction "PIN-2_SW2") (pintype "passive"))
    )
    (net (code "78") (name "Net-(S94A-PIN-1)") (class "Default")
      (node (ref "JB94") (pin "2") (pinfunction "2_2") (pintype "passive"))
      (node (ref "S94") (pin "SW1") (pinfunction "PIN-1_SW1") (pintype "passive"))
    )
    (net (code "79") (name "Net-(S94A-PIN-2)") (class "Default")
      (node (ref "JA94") (pin "1") (pinfunction "1_1") (pintype "passive"))
      (node (ref "S94") (pin "SW2") (pinfunction "PIN-2_SW2") (pintype "passive"))
    )
    (net (code "80") (name "Net-(S95A-PIN-1)") (class "Default")
      (node (ref "JB95") (pin "2") (pinfunction "2_2") (pintype "passive"))
      (node (ref "S95") (pin "SW1") (pinfunction "PIN-1_SW1") (pintype "passive"))
    )
    (net (code "81") (name "Net-(S95A-PIN-2)") (class "Default")
      (node (ref "JA95") (pin "1") (pinfunction "1_1") (pintype "passive"))
      (node (ref "S95") (pin "SW2") (pinfunction "PIN-2_SW2") (pintype "passive"))
    )
    (net (code "82") (name "Net-(S96A-PIN-1)") (class "Default")
      (node (ref "JB96") (pin "2") (pinfunction "2_2") (pintype "passive"))
      (node (ref "S96") (pin "SW1") (pinfunction "PIN-1_SW1") (pintype "passive"))
    )
    (net (code "83") (name "Net-(S96A-PIN-2)") (class "Default")
      (node (ref "JA96") (pin "1") (pinfunction "1_1") (pintype "passive"))
      (node (ref "S96") (pin "SW2") (pinfunction "PIN-2_SW2") (pintype "passive"))
    )
    (net (code "84") (name "Net-(S97A-PIN-1)") (class "Default")
      (node (ref "JB97") (pin "2") (pinfunction "2_2") (pintype "passive"))
      (node (ref "S97") (pin "SW1") (pinfunction "PIN-1_SW1") (pintype "passive"))
    )
    (net (code "85") (name "Net-(S97A-PIN-2)") (class "Default")
      (node (ref "JA97") (pin "1") (pinfunction "1_1") (pintype "passive"))
      (node (ref "S97") (pin "SW2") (pinfunction "PIN-2_SW2") (pintype "passive"))
    )
    (net (code "86") (name "Net-(S98A-PIN-1)") (class "Default")
      (node (ref "JB98") (pin "2") (pinfunction "2_2") (pintype "passive"))
      (node (ref "S98") (pin "SW1") (pinfunction "PIN-1_SW1") (pintype "passive"))
    )
    (net (code "87") (name "Net-(S98A-PIN-2)") (class "Default")
      (node (ref "JA98") (pin "1") (pinfunction "1_1") (pintype "passive"))
      (node (ref "S98") (pin "SW2") (pinfunction "PIN-2_SW2") (pintype "passive"))
    )
    (net (code "88") (name "Net-(S99A-PIN-1)") (class "Default")
      (node (ref "JB99") (pin "2") (pinfunction "2_2") (pintype "passive"))
      (node (ref "S99") (pin "SW1") (pinfunction "PIN-1_SW1") (pintype "passive"))
    )
    (net (code "89") (name "Net-(S99A-PIN-2)") (class "Default")
      (node (ref "JA99") (pin "1") (pinfunction "1_1") (pintype "passive"))
      (node (ref "S99") (pin "SW2") (pinfunction "PIN-2_SW2") (pintype "passive"))
    )
    (net (code "90") (name "Net-(S100A-PIN-1)") (class "Default")
      (node (ref "JB100") (pin "2") (pinfunction "2_2") (pintype "passive"))
      (node (ref "S100") (pin "SW1") (pinfunction "PIN-1_SW1") (pintype "passive"))
    )
    (net (code "91") (name "Net-(S100A-PIN-2)") (class "Default")
      (node (ref "JA100") (pin "1") (pinfunction "1_1") (pintype "passive"))
      (node (ref "S100") (pin "SW2") (pinfunction "PIN-2_SW2") (pintype "passive"))
    )
    (net (code "92") (name "Net-(S101A-PIN-1)") (class "Default")
      (node (ref "JB101") (pin "2") (pinfunction "2_2") (pintype "passive"))
      (node (ref "S101") (pin "SW1") (pinfunction "PIN-1_SW1") (pintype "passive"))
    )
    (net (code "93") (name "Net-(S101A-PIN-2)") (class "Default")
      (node (ref "JA101") (pin "1") (pinfunction "1_1") (pintype "passive"))
      (node (ref "S101") (pin "SW2") (pinfunction "PIN-2_SW2") (pintype "passive"))
    )
    (net (code "94") (name "Net-(S102A-PIN-1)") (class "Default")
      (node (ref "JB102") (pin "2") (pinfunction "2_2") (pintype "passive"))
      (node (ref "S102") (pin "SW1") (pinfunction "PIN-1_SW1") (pintype "passive"))
    )
    (net (code "95") (name "Net-(S102A-PIN-2)") (class "Default")
      (node (ref "JA102") (pin "1") (pinfunction "1_1") (pintype "passive"))
      (node (ref "S102") (pin "SW2") (pinfunction "PIN-2_SW2") (pintype "passive"))
    )
    (net (code "96") (name "Net-(S103A-PIN-1)") (class "Default")
      (node (ref "JB103") (pin "2") (pinfunction "2_2") (pintype "passive"))
      (node (ref "S103") (pin "SW1") (pinfunction "PIN-1_SW1") (pintype "passive"))
    )
    (net (code "97") (name "Net-(S103A-PIN-2)") (class "Default")
      (node (ref "JA103") (pin "1") (pinfunction "1_1") (pintype "passive"))
      (node (ref "S103") (pin "SW2") (pinfunction "PIN-2_SW2") (pintype "passive"))
    )
    (net (code "98") (name "Net-(S104A-PIN-1)") (class "Default")
      (node (ref "JB104") (pin "2") (pinfunction "2_2") (pintype "passive"))
      (node (ref "S104") (pin "SW1") (pinfunction "PIN-1_SW1") (pintype "passive"))
    )
    (net (code "99") (name "Net-(S104A-PIN-2)") (class "Default")
      (node (ref "JA104") (pin "1") (pinfunction "1_1") (pintype "passive"))
      (node (ref "S104") (pin "SW2") (pinfunction "PIN-2_SW2") (pintype "passive"))
    )
    (net (code "100") (name "Net-(S105A-PIN-1)") (class "Default")
      (node (ref "JB105") (pin "2") (pinfunction "2_2") (pintype "passive"))
      (node (ref "S105") (pin "SW1") (pinfunction "PIN-1_SW1") (pintype "passive"))
    )
    (net (code "101") (name "Net-(S105A-PIN-2)") (class "Default")
      (node (ref "JA105") (pin "1") (pinfunction "1_1") (pintype "passive"))
      (node (ref "S105") (pin "SW2") (pinfunction "PIN-2_SW2") (pintype "passive"))
    )
    (net (code "102") (name "Net-(S106A-PIN-1)") (class "Default")
      (node (ref "JB106") (pin "2") (pinfunction "2_2") (pintype "passive"))
      (node (ref "S106") (pin "SW1") (pinfunction "PIN-1_SW1") (pintype "passive"))
    )
    (net (code "103") (name "Net-(S106A-PIN-2)") (class "Default")
      (node (ref "JA106") (pin "1") (pinfunction "1_1") (pintype "passive"))
      (node (ref "S106") (pin "SW2") (pinfunction "PIN-2_SW2") (pintype "passive"))
    )
    (net (code "104") (name "Net-(S107A-PIN-1)") (class "Default")
      (node (ref "JB107") (pin "2") (pinfunction "2_2") (pintype "passive"))
      (node (ref "S107") (pin "SW1") (pinfunction "PIN-1_SW1") (pintype "passive"))
      (node (ref "S107B") (pin "SW1") (pinfunction "PIN-1_SW1") (pintype "passive"))
    )
    (net (code "105") (name "Net-(S107A-PIN-2)") (class "Default")
      (node (ref "JA107") (pin "1") (pinfunction "1_1") (pintype "passive"))
      (node (ref "S107") (pin "SW2") (pinfunction "PIN-2_SW2") (pintype "passive"))
      (node (ref "S107B") (pin "SW2") (pinfunction "PIN-2_SW2") (pintype "passive"))
    )
    (net (code "106") (name "Net-(S108A-PIN-1)") (class "Default")
      (node (ref "JB108") (pin "2") (pinfunction "2_2") (pintype "passive"))
      (node (ref "S108") (pin "SW1") (pinfunction "PIN-1_SW1") (pintype "passive"))
    )
    (net (code "107") (name "Net-(S108A-PIN-2)") (class "Default")
      (node (ref "JA108") (pin "1") (pinfunction "1_1") (pintype "passive"))
      (node (ref "S108") (pin "SW2") (pinfunction "PIN-2_SW2") (pintype "passive"))
    )
    (net (code "108") (name "Net-(S109A-PIN-1)") (class "Default")
      (node (ref "JB109") (pin "2") (pinfunction "2_2") (pintype "passive"))
      (node (ref "S109") (pin "SW1") (pinfunction "PIN-1_SW1") (pintype "passive"))
    )
    (net (code "109") (name "Net-(S109A-PIN-2)") (class "Default")
      (node (ref "JA109") (pin "1") (pinfunction "1_1") (pintype "passive"))
      (node (ref "S109") (pin "SW2") (pinfunction "PIN-2_SW2") (pintype "passive"))
    )
    (net (code "110") (name "Net-(S110A-PIN-1)") (class "Default")
      (node (ref "JB110") (pin "2") (pinfunction "2_2") (pintype "passive"))
      (node (ref "S110") (pin "SW1") (pinfunction "PIN-1_SW1") (pintype "passive"))
    )
    (net (code "111") (name "Net-(S110A-PIN-2)") (class "Default")
      (node (ref "JA110") (pin "1") (pinfunction "1_1") (pintype "passive"))
      (node (ref "S110") (pin "SW2") (pinfunction "PIN-2_SW2") (pintype "passive"))
    )
  )
)
